# HitBoxV0_31-Powaa.net
KiCad netlist of a schematic drawn in EAGLE
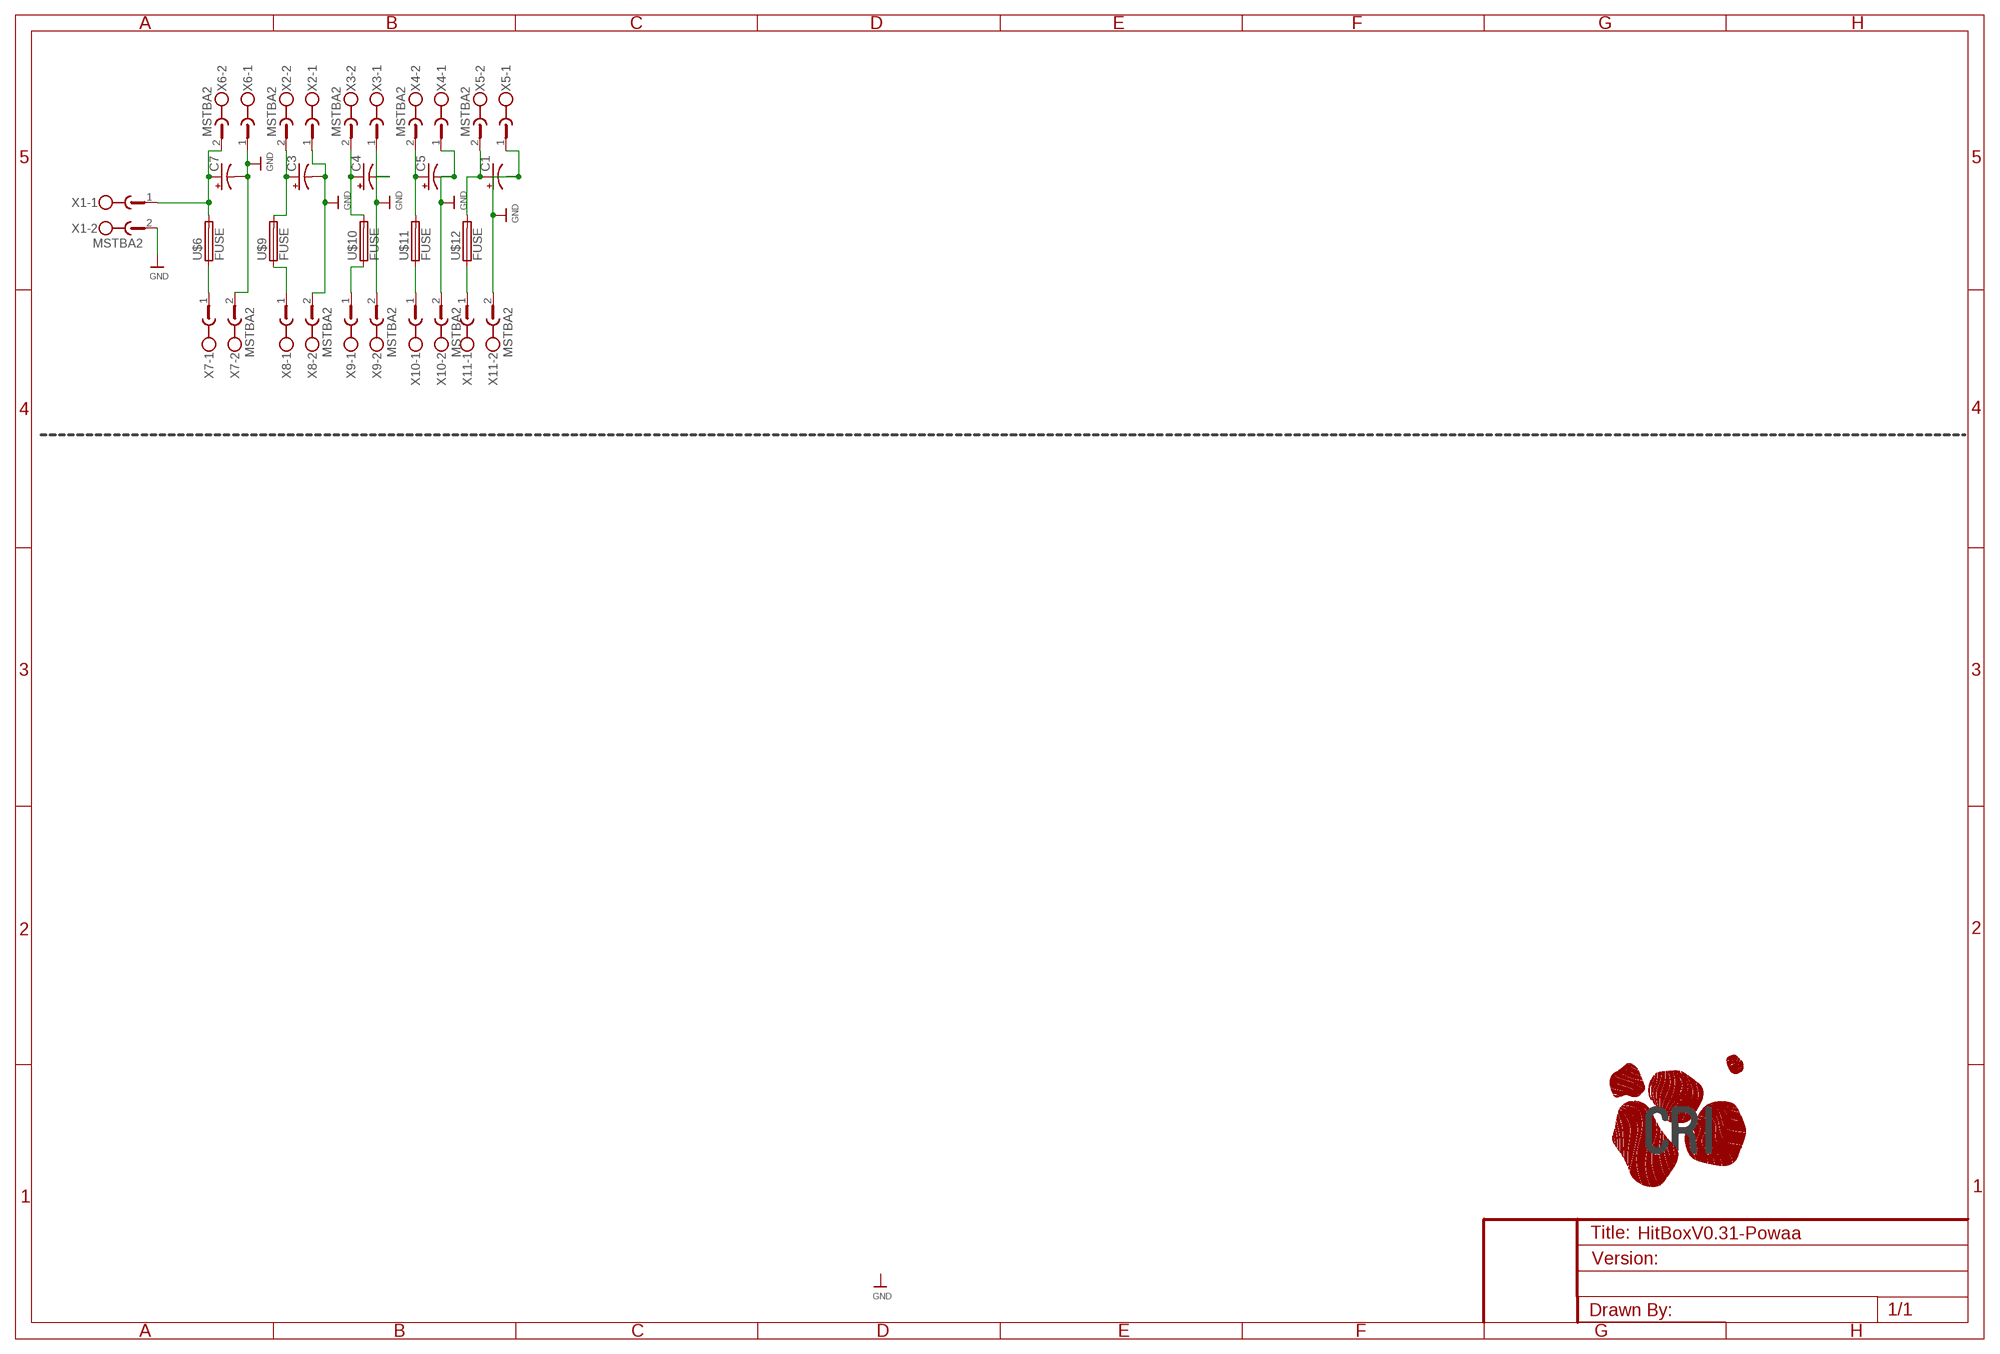
[diagram p0: schematic, sheet 1]

(export (version "E")
  (design (tool "Eeschema 10.0.6"))
  (components
    (comp (ref "C1")
      (value "CPOL-USE2,5-6E")
      (footprint "eagle-import:E2,5-6E")
      (libsource (lib "eagle-import") (part "CPOL-USE2,5-6E"))
    )
    (comp (ref "C3")
      (value "CPOL-USE2,5-6E")
      (footprint "eagle-import:E2,5-6E")
      (libsource (lib "eagle-import") (part "CPOL-USE2,5-6E"))
    )
    (comp (ref "C4")
      (value "CPOL-USE2,5-6E")
      (footprint "eagle-import:E2,5-6E")
      (libsource (lib "eagle-import") (part "CPOL-USE2,5-6E"))
    )
    (comp (ref "C5")
      (value "CPOL-USE2,5-6E")
      (footprint "eagle-import:E2,5-6E")
      (libsource (lib "eagle-import") (part "CPOL-USE2,5-6E"))
    )
    (comp (ref "C7")
      (value "CPOL-USE2,5-6E")
      (footprint "eagle-import:E2,5-6E")
      (libsource (lib "eagle-import") (part "CPOL-USE2,5-6E"))
    )
    (comp (ref "U$6")
      (value "FUSE")
      (footprint "eagle-import:KEYSTONE-AUTO-FUSE")
      (libsource (lib "eagle-import") (part "FUSE"))
    )
    (comp (ref "U$7")
      (value "LOGO-CRI-NEW-130MMX30MM-TPLACE")
      (footprint "eagle-import:LOGO_CRI-NEW-BMP30MM-TOP")
      (libsource (lib "eagle-import") (part "LOGO-CRI-NEW-130MMX30MM-TPLACE"))
    )
    (comp (ref "U$9")
      (value "FUSE")
      (footprint "eagle-import:KEYSTONE-AUTO-FUSE")
      (libsource (lib "eagle-import") (part "FUSE"))
    )
    (comp (ref "U$10")
      (value "FUSE")
      (footprint "eagle-import:KEYSTONE-AUTO-FUSE")
      (libsource (lib "eagle-import") (part "FUSE"))
    )
    (comp (ref "U$11")
      (value "FUSE")
      (footprint "eagle-import:KEYSTONE-AUTO-FUSE")
      (libsource (lib "eagle-import") (part "FUSE"))
    )
    (comp (ref "U$12")
      (value "FUSE")
      (footprint "eagle-import:KEYSTONE-AUTO-FUSE")
      (libsource (lib "eagle-import") (part "FUSE"))
    )
    (comp (ref "X1")
      (value "MSTBA2")
      (footprint "eagle-import:MSTBA2")
      (fields (field (name "MF") "FARNELL") (field (name "MPN") "1757242"))
      (libsource (lib "eagle-import") (part "MSTBA2"))
    )
    (comp (ref "X2")
      (value "MSTBA2")
      (footprint "eagle-import:MSTBA2")
      (fields (field (name "MF") "FARNELL") (field (name "MPN") "1757242"))
      (libsource (lib "eagle-import") (part "MSTBA2"))
    )
    (comp (ref "X3")
      (value "MSTBA2")
      (footprint "eagle-import:MSTBA2")
      (fields (field (name "MF") "FARNELL") (field (name "MPN") "1757242"))
      (libsource (lib "eagle-import") (part "MSTBA2"))
    )
    (comp (ref "X4")
      (value "MSTBA2")
      (footprint "eagle-import:MSTBA2")
      (fields (field (name "MF") "FARNELL") (field (name "MPN") "1757242"))
      (libsource (lib "eagle-import") (part "MSTBA2"))
    )
    (comp (ref "X5")
      (value "MSTBA2")
      (footprint "eagle-import:MSTBA2")
      (fields (field (name "MF") "FARNELL") (field (name "MPN") "1757242"))
      (libsource (lib "eagle-import") (part "MSTBA2"))
    )
    (comp (ref "X6")
      (value "MSTBA2")
      (footprint "eagle-import:MSTBA2")
      (fields (field (name "MF") "FARNELL") (field (name "MPN") "1757242"))
      (libsource (lib "eagle-import") (part "MSTBA2"))
    )
    (comp (ref "X7")
      (value "MSTBA2")
      (footprint "eagle-import:MSTBA2")
      (fields (field (name "MF") "FARNELL") (field (name "MPN") "1757242"))
      (libsource (lib "eagle-import") (part "MSTBA2"))
    )
    (comp (ref "X8")
      (value "MSTBA2")
      (footprint "eagle-import:MSTBA2")
      (fields (field (name "MF") "FARNELL") (field (name "MPN") "1757242"))
      (libsource (lib "eagle-import") (part "MSTBA2"))
    )
    (comp (ref "X9")
      (value "MSTBA2")
      (footprint "eagle-import:MSTBA2")
      (fields (field (name "MF") "FARNELL") (field (name "MPN") "1757242"))
      (libsource (lib "eagle-import") (part "MSTBA2"))
    )
    (comp (ref "X10")
      (value "MSTBA2")
      (footprint "eagle-import:MSTBA2")
      (fields (field (name "MF") "FARNELL") (field (name "MPN") "1757242"))
      (libsource (lib "eagle-import") (part "MSTBA2"))
    )
    (comp (ref "X11")
      (value "MSTBA2")
      (footprint "eagle-import:MSTBA2")
      (fields (field (name "MF") "FARNELL") (field (name "MPN") "1757242"))
      (libsource (lib "eagle-import") (part "MSTBA2"))
    )
  )
  (nets
    (net (code "1") (name "GND") (class "Default")
      (node (ref "C1") (pin "-") (pinfunction "-_-") (pintype "passive"))
      (node (ref "C3") (pin "-") (pinfunction "-_-") (pintype "passive"))
      (node (ref "C4") (pin "-") (pinfunction "-_-") (pintype "passive"))
      (node (ref "C5") (pin "-") (pinfunction "-_-") (pintype "passive"))
      (node (ref "C7") (pin "-") (pinfunction "-_-") (pintype "passive"))
      (node (ref "X1") (pin "2") (pinfunction "1_2") (pintype "passive"))
      (node (ref "X10") (pin "2") (pinfunction "1_2") (pintype "passive"))
      (node (ref "X11") (pin "2") (pinfunction "1_2") (pintype "passive"))
      (node (ref "X2") (pin "1") (pinfunction "1_1") (pintype "passive"))
      (node (ref "X3") (pin "1") (pinfunction "1_1") (pintype "passive"))
      (node (ref "X4") (pin "1") (pinfunction "1_1") (pintype "passive"))
      (node (ref "X5") (pin "1") (pinfunction "1_1") (pintype "passive"))
      (node (ref "X6") (pin "1") (pinfunction "1_1") (pintype "passive"))
      (node (ref "X7") (pin "2") (pinfunction "1_2") (pintype "passive"))
      (node (ref "X8") (pin "2") (pinfunction "1_2") (pintype "passive"))
      (node (ref "X9") (pin "2") (pinfunction "1_2") (pintype "passive"))
    )
    (net (code "2") (name "Net-(U$6-1-PadP$1)") (class "Default")
      (node (ref "U$6") (pin "P$1") (pinfunction "1_P$1") (pintype "passive"))
      (node (ref "U$6") (pin "P$2") (pinfunction "1_P$2") (pintype "passive"))
      (node (ref "X7") (pin "1") (pinfunction "1_1") (pintype "passive"))
    )
    (net (code "3") (name "Net-(U$9-1-PadP$1)") (class "Default")
      (node (ref "U$9") (pin "P$1") (pinfunction "1_P$1") (pintype "passive"))
      (node (ref "U$9") (pin "P$2") (pinfunction "1_P$2") (pintype "passive"))
      (node (ref "X8") (pin "1") (pinfunction "1_1") (pintype "passive"))
    )
    (net (code "4") (name "Net-(U$10-1-PadP$1)") (class "Default")
      (node (ref "U$10") (pin "P$1") (pinfunction "1_P$1") (pintype "passive"))
      (node (ref "U$10") (pin "P$2") (pinfunction "1_P$2") (pintype "passive"))
      (node (ref "X9") (pin "1") (pinfunction "1_1") (pintype "passive"))
    )
    (net (code "5") (name "Net-(U$11-1-PadP$1)") (class "Default")
      (node (ref "U$11") (pin "P$1") (pinfunction "1_P$1") (pintype "passive"))
      (node (ref "U$11") (pin "P$2") (pinfunction "1_P$2") (pintype "passive"))
      (node (ref "X10") (pin "1") (pinfunction "1_1") (pintype "passive"))
    )
    (net (code "6") (name "Net-(U$12-1-PadP$1)") (class "Default")
      (node (ref "U$12") (pin "P$1") (pinfunction "1_P$1") (pintype "passive"))
      (node (ref "U$12") (pin "P$2") (pinfunction "1_P$2") (pintype "passive"))
      (node (ref "X11") (pin "1") (pinfunction "1_1") (pintype "passive"))
    )
    (net (code "7") (name "Net-(X2B-1)") (class "Default")
      (node (ref "C3") (pin "+") (pinfunction "+_+") (pintype "passive"))
      (node (ref "U$9") (pin "P$3") (pinfunction "2_P$3") (pintype "passive"))
      (node (ref "U$9") (pin "P$4") (pinfunction "2_P$4") (pintype "passive"))
      (node (ref "X2") (pin "2") (pinfunction "1_2") (pintype "passive"))
    )
    (net (code "8") (name "Net-(X3B-1)") (class "Default")
      (node (ref "C4") (pin "+") (pinfunction "+_+") (pintype "passive"))
      (node (ref "U$10") (pin "P$3") (pinfunction "2_P$3") (pintype "passive"))
      (node (ref "U$10") (pin "P$4") (pinfunction "2_P$4") (pintype "passive"))
      (node (ref "X3") (pin "2") (pinfunction "1_2") (pintype "passive"))
    )
    (net (code "9") (name "Net-(X4B-1)") (class "Default")
      (node (ref "C5") (pin "+") (pinfunction "+_+") (pintype "passive"))
      (node (ref "U$11") (pin "P$3") (pinfunction "2_P$3") (pintype "passive"))
      (node (ref "U$11") (pin "P$4") (pinfunction "2_P$4") (pintype "passive"))
      (node (ref "X4") (pin "2") (pinfunction "1_2") (pintype "passive"))
    )
    (net (code "10") (name "Net-(X5B-1)") (class "Default")
      (node (ref "C1") (pin "+") (pinfunction "+_+") (pintype "passive"))
      (node (ref "U$12") (pin "P$3") (pinfunction "2_P$3") (pintype "passive"))
      (node (ref "U$12") (pin "P$4") (pinfunction "2_P$4") (pintype "passive"))
      (node (ref "X5") (pin "2") (pinfunction "1_2") (pintype "passive"))
    )
    (net (code "11") (name "Net-(X6B-1)") (class "Default")
      (node (ref "C7") (pin "+") (pinfunction "+_+") (pintype "passive"))
      (node (ref "U$6") (pin "P$3") (pinfunction "2_P$3") (pintype "passive"))
      (node (ref "U$6") (pin "P$4") (pinfunction "2_P$4") (pintype "passive"))
      (node (ref "X1") (pin "1") (pinfunction "1_1") (pintype "passive"))
      (node (ref "X6") (pin "2") (pinfunction "1_2") (pintype "passive"))
    )
  )
)
